# Board_V03.net
KiCad netlist of a schematic drawn in EAGLE
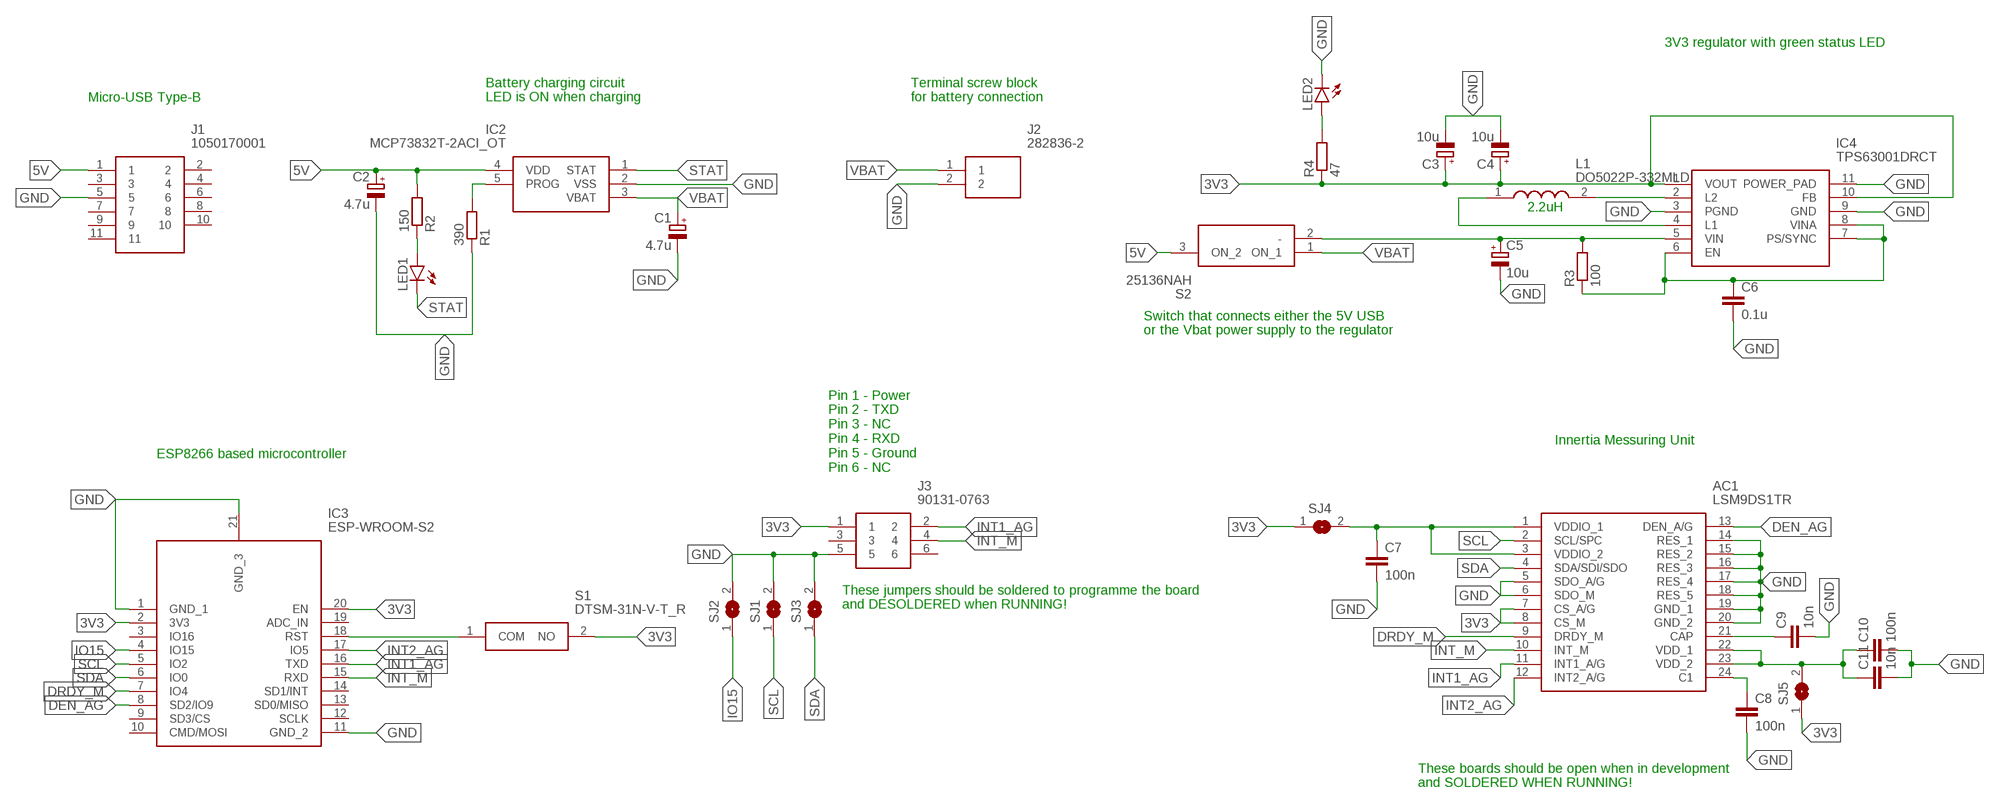
[diagram p0: schematic, sheet 1]

(export (version "E")
  (design (tool "Eeschema 10.0.6"))
  (components
    (comp (ref "AC1")
      (value "LSM9DS1TR")
      (footprint "eagle-import:LGA-24L(3X3.5X1MM)")
      (fields (field (name "MOUSER_PART_NUMBER") "511-LSM9DS1TR") (field (name "RS_PART_NUMBER") "1660908"))
      (libsource (lib "eagle-import") (part "LSM9DS1TR"))
    )
    (comp (ref "C1")
      (value "4.7u")
      (footprint "eagle-import:D_7343-31R")
      (libsource (lib "eagle-import") (part "CPOL-EUD/7343-31R"))
    )
    (comp (ref "C2")
      (value "4.7u")
      (footprint "eagle-import:D_7343-31R")
      (libsource (lib "eagle-import") (part "CPOL-EUD/7343-31R"))
    )
    (comp (ref "C3")
      (value "10u")
      (footprint "eagle-import:D_7343-31R")
      (libsource (lib "eagle-import") (part "CPOL-EUD/7343-31R"))
    )
    (comp (ref "C4")
      (value "10u")
      (footprint "eagle-import:D_7343-31R")
      (libsource (lib "eagle-import") (part "CPOL-EUD/7343-31R"))
    )
    (comp (ref "C5")
      (value "10u")
      (footprint "eagle-import:D_7343-31R")
      (libsource (lib "eagle-import") (part "CPOL-EUD/7343-31R"))
    )
    (comp (ref "C6")
      (value "0.1u")
      (footprint "eagle-import:C0402")
      (libsource (lib "eagle-import") (part "C-EUC0402"))
    )
    (comp (ref "C7")
      (value "100n")
      (footprint "eagle-import:C0805")
      (libsource (lib "eagle-import") (part "C-EUC0805"))
    )
    (comp (ref "C8")
      (value "100n")
      (footprint "eagle-import:C0805")
      (libsource (lib "eagle-import") (part "C-EUC0805"))
    )
    (comp (ref "C9")
      (value "10n")
      (footprint "eagle-import:C0805")
      (libsource (lib "eagle-import") (part "C-EUC0805"))
    )
    (comp (ref "C10")
      (value "100n")
      (footprint "eagle-import:C0805")
      (libsource (lib "eagle-import") (part "C-EUC0805"))
    )
    (comp (ref "C11")
      (value "10n")
      (footprint "eagle-import:C0805")
      (libsource (lib "eagle-import") (part "C-EUC0805"))
    )
    (comp (ref "IC2")
      (value "MCP73832T-2ACI_OT")
      (footprint "eagle-import:SOT95P270X145-5N")
      (fields
        (field (name "MANUFACTURER_PART_NUMBER") "MCP73832T-2ACI/OT")
        (field (name "MOUSER_PART_NUMBER") "579-MCP73832T-2ACIOT")
        (field (name "RS_PART_NUMBER") "9122897")
      )
      (libsource (lib "eagle-import") (part "MCP73832T-2ACI_OT"))
    )
    (comp (ref "IC3")
      (value "ESP-WROOM-S2")
      (footprint "eagle-import:QFN150P1600X1700X315-21N")
      (libsource (lib "eagle-import") (part "ESP-WROOM-S2"))
    )
    (comp (ref "IC4")
      (value "TPS63001DRCT")
      (footprint "eagle-import:SON50P300X300X100-11N")
      (fields (field (name "RS_PART_NUMBER") "7968405"))
      (libsource (lib "eagle-import") (part "TPS63001DRCT"))
    )
    (comp (ref "J1")
      (value "1050170001")
      (footprint "eagle-import:MICROUSB-BTYPE")
      (libsource (lib "eagle-import") (part "1050170001"))
    )
    (comp (ref "J2")
      (value "282836-2")
      (footprint "eagle-import:SHDR2W100P0X500_1X2_1000X820X1")
      (fields (field (name "MOUSER_PART_NUMBER") "571-2828362") (field (name "RS_PART_NUMBER") "1354983"))
      (libsource (lib "eagle-import") (part "282836-2"))
    )
    (comp (ref "J3")
      (value "90131-0763")
      (footprint "eagle-import:HDRV6W90P254_2X3_762X500X560P")
      (fields (field (name "MOUSER_PART_NUMBER") "538-90131-0763") (field (name "RS_PART_NUMBER") "3606443P"))
      (libsource (lib "eagle-import") (part "90131-0763"))
    )
    (comp (ref "L1")
      (value "DO5022P-332MLD")
      (footprint "eagle-import:DO5022P-104MLD")
      (fields (field (name "MOUSER_PART_NUMBER") "994-DO5022P-332MLD"))
      (libsource (lib "eagle-import") (part "DO5022P-332MLD"))
    )
    (comp (ref "LED1")
      (value "LED5MM")
      (footprint "eagle-import:LED5MM")
      (libsource (lib "eagle-import") (part "LED5MM"))
    )
    (comp (ref "LED2")
      (value "LED5MM")
      (footprint "eagle-import:LED5MM")
      (libsource (lib "eagle-import") (part "LED5MM"))
    )
    (comp (ref "R1")
      (value "390")
      (footprint "eagle-import:R0805")
      (libsource (lib "eagle-import") (part "R-EU_R0805"))
    )
    (comp (ref "R2")
      (value "150")
      (footprint "eagle-import:R0805")
      (libsource (lib "eagle-import") (part "R-EU_R0805"))
    )
    (comp (ref "R3")
      (value "100")
      (footprint "eagle-import:R0805")
      (libsource (lib "eagle-import") (part "R-EU_R0805"))
    )
    (comp (ref "R4")
      (value "47")
      (footprint "eagle-import:R0805")
      (libsource (lib "eagle-import") (part "R-EU_R0805"))
    )
    (comp (ref "S1")
      (value "DTSM-31N-V-T_R")
      (footprint "eagle-import:DTSM32NVTR")
      (fields
        (field (name "MANUFACTURER_PART_NUMBER") "DTSM-31N-V-T/R")
        (field (name "MOUSER_PART_NUMBER") "113-DTSM31NVTR")
      )
      (libsource (lib "eagle-import") (part "DTSM-31N-V-T_R"))
    )
    (comp (ref "S2")
      (value "25136NAH")
      (footprint "eagle-import:25136NAH")
      (fields (field (name "MOUSER_PART_NUMBER") "642-25136NAH") (field (name "RS_PART_NUMBER") "0339673A"))
      (libsource (lib "eagle-import") (part "25136NAH"))
    )
    (comp (ref "SJ1")
      (value "SJW")
      (footprint "eagle-import:SJW")
      (libsource (lib "eagle-import") (part "SJW"))
    )
    (comp (ref "SJ2")
      (value "SJW")
      (footprint "eagle-import:SJW")
      (libsource (lib "eagle-import") (part "SJW"))
    )
    (comp (ref "SJ3")
      (value "SJW")
      (footprint "eagle-import:SJW")
      (libsource (lib "eagle-import") (part "SJW"))
    )
    (comp (ref "SJ4")
      (value "SJW")
      (footprint "eagle-import:SJW")
      (libsource (lib "eagle-import") (part "SJW"))
    )
    (comp (ref "SJ5")
      (value "SJW")
      (footprint "eagle-import:SJW")
      (libsource (lib "eagle-import") (part "SJW"))
    )
  )
  (nets
    (net (code "1") (name "3V3") (class "Default")
      (node (ref "AC1") (pin "7") (pinfunction "CS_A/G_7") (pintype "bidirectional"))
      (node (ref "AC1") (pin "8") (pinfunction "CS_M_8") (pintype "bidirectional"))
      (node (ref "C3") (pin "+") (pinfunction "+_+") (pintype "passive"))
      (node (ref "C4") (pin "+") (pinfunction "+_+") (pintype "passive"))
      (node (ref "IC3") (pin "2") (pinfunction "3V3_2") (pintype "power_in"))
      (node (ref "IC3") (pin "20") (pinfunction "EN_20") (pintype "bidirectional"))
      (node (ref "IC4") (pin "1") (pinfunction "VOUT_1") (pintype "bidirectional"))
      (node (ref "IC4") (pin "10") (pinfunction "FB_10") (pintype "bidirectional"))
      (node (ref "J3") (pin "1") (pinfunction "1_1") (pintype "bidirectional"))
      (node (ref "R4") (pin "1") (pinfunction "1_1") (pintype "passive"))
      (node (ref "S1") (pin "2") (pinfunction "NO_2") (pintype "bidirectional"))
      (node (ref "SJ4") (pin "1") (pinfunction "1_1") (pintype "passive"))
      (node (ref "SJ5") (pin "1") (pinfunction "1_1") (pintype "passive"))
    )
    (net (code "2") (name "5V") (class "Default")
      (node (ref "C2") (pin "+") (pinfunction "+_+") (pintype "passive"))
      (node (ref "IC2") (pin "4") (pinfunction "VDD_4") (pintype "power_in"))
      (node (ref "J1") (pin "1") (pinfunction "1_1") (pintype "bidirectional"))
      (node (ref "R2") (pin "2") (pinfunction "2_2") (pintype "passive"))
      (node (ref "S2") (pin "3") (pinfunction "ON_2_3") (pintype "bidirectional"))
    )
    (net (code "3") (name "DEN_AG") (class "Default")
      (node (ref "AC1") (pin "13") (pinfunction "DEN_A/G_13") (pintype "bidirectional"))
      (node (ref "IC3") (pin "8") (pinfunction "SD2/IO9_8") (pintype "bidirectional"))
    )
    (net (code "4") (name "DRDY_M") (class "Default")
      (node (ref "AC1") (pin "9") (pinfunction "DRDY_M_9") (pintype "bidirectional"))
      (node (ref "IC3") (pin "7") (pinfunction "IO4_7") (pintype "bidirectional"))
    )
    (net (code "5") (name "GND") (class "Default")
      (node (ref "AC1") (pin "14") (pinfunction "RES_1_14") (pintype "power_in"))
      (node (ref "AC1") (pin "15") (pinfunction "RES_2_15") (pintype "power_in"))
      (node (ref "AC1") (pin "16") (pinfunction "RES_3_16") (pintype "power_in"))
      (node (ref "AC1") (pin "17") (pinfunction "RES_4_17") (pintype "power_in"))
      (node (ref "AC1") (pin "18") (pinfunction "RES_5_18") (pintype "power_in"))
      (node (ref "AC1") (pin "19") (pinfunction "GND_1_19") (pintype "power_in"))
      (node (ref "AC1") (pin "20") (pinfunction "GND_2_20") (pintype "power_in"))
      (node (ref "AC1") (pin "5") (pinfunction "SDO_A/G_5") (pintype "output"))
      (node (ref "AC1") (pin "6") (pinfunction "SDO_M_6") (pintype "output"))
      (node (ref "C1") (pin "-") (pinfunction "-_-") (pintype "passive"))
      (node (ref "C10") (pin "2") (pinfunction "2_2") (pintype "passive"))
      (node (ref "C11") (pin "2") (pinfunction "2_2") (pintype "passive"))
      (node (ref "C2") (pin "-") (pinfunction "-_-") (pintype "passive"))
      (node (ref "C3") (pin "-") (pinfunction "-_-") (pintype "passive"))
      (node (ref "C4") (pin "-") (pinfunction "-_-") (pintype "passive"))
      (node (ref "C5") (pin "-") (pinfunction "-_-") (pintype "passive"))
      (node (ref "C6") (pin "2") (pinfunction "2_2") (pintype "passive"))
      (node (ref "C7") (pin "2") (pinfunction "2_2") (pintype "passive"))
      (node (ref "C8") (pin "2") (pinfunction "2_2") (pintype "passive"))
      (node (ref "C9") (pin "2") (pinfunction "2_2") (pintype "passive"))
      (node (ref "IC2") (pin "2") (pinfunction "VSS_2") (pintype "power_in"))
      (node (ref "IC3") (pin "1") (pinfunction "GND_1_1") (pintype "power_in"))
      (node (ref "IC3") (pin "11") (pinfunction "GND_2_11") (pintype "power_in"))
      (node (ref "IC3") (pin "21") (pinfunction "GND_3_21") (pintype "power_in"))
      (node (ref "IC4") (pin "11") (pinfunction "POWER_PAD_11") (pintype "bidirectional"))
      (node (ref "IC4") (pin "3") (pinfunction "PGND_3") (pintype "bidirectional"))
      (node (ref "IC4") (pin "9") (pinfunction "GND_9") (pintype "bidirectional"))
      (node (ref "J1") (pin "5") (pinfunction "5_5") (pintype "bidirectional"))
      (node (ref "J2") (pin "2") (pinfunction "2_2") (pintype "bidirectional"))
      (node (ref "J3") (pin "5") (pinfunction "5_5") (pintype "bidirectional"))
      (node (ref "LED2") (pin "K") (pinfunction "C_K") (pintype "passive"))
      (node (ref "R1") (pin "1") (pinfunction "1_1") (pintype "passive"))
      (node (ref "SJ1") (pin "2") (pinfunction "2_2") (pintype "passive"))
      (node (ref "SJ2") (pin "2") (pinfunction "2_2") (pintype "passive"))
      (node (ref "SJ3") (pin "2") (pinfunction "2_2") (pintype "passive"))
    )
    (net (code "6") (name "INT1_AG") (class "Default")
      (node (ref "AC1") (pin "11") (pinfunction "INT1_A/G_11") (pintype "bidirectional"))
      (node (ref "IC3") (pin "16") (pinfunction "TXD_16") (pintype "bidirectional"))
      (node (ref "J3") (pin "2") (pinfunction "2_2") (pintype "bidirectional"))
    )
    (net (code "7") (name "INT2_AG") (class "Default")
      (node (ref "AC1") (pin "12") (pinfunction "INT2_A/G_12") (pintype "bidirectional"))
      (node (ref "IC3") (pin "17") (pinfunction "IO5_17") (pintype "bidirectional"))
    )
    (net (code "8") (name "INT_M") (class "Default")
      (node (ref "AC1") (pin "10") (pinfunction "INT_M_10") (pintype "bidirectional"))
      (node (ref "IC3") (pin "15") (pinfunction "RXD_15") (pintype "bidirectional"))
      (node (ref "J3") (pin "4") (pinfunction "4_4") (pintype "bidirectional"))
    )
    (net (code "9") (name "IO15") (class "Default")
      (node (ref "IC3") (pin "4") (pinfunction "IO15_4") (pintype "bidirectional"))
      (node (ref "SJ2") (pin "1") (pinfunction "1_1") (pintype "passive"))
    )
    (net (code "10") (name "Net-(AC1-C1)") (class "Default")
      (node (ref "AC1") (pin "24") (pinfunction "C1_24") (pintype "bidirectional"))
      (node (ref "C8") (pin "1") (pinfunction "1_1") (pintype "passive"))
    )
    (net (code "11") (name "Net-(AC1-CAP)") (class "Default")
      (node (ref "AC1") (pin "21") (pinfunction "CAP_21") (pintype "power_in"))
      (node (ref "C9") (pin "1") (pinfunction "1_1") (pintype "passive"))
    )
    (net (code "12") (name "Net-(AC1-VDDIO_1)") (class "Default")
      (node (ref "AC1") (pin "1") (pinfunction "VDDIO_1_1") (pintype "power_in"))
      (node (ref "AC1") (pin "3") (pinfunction "VDDIO_2_3") (pintype "power_in"))
      (node (ref "C7") (pin "1") (pinfunction "1_1") (pintype "passive"))
      (node (ref "SJ4") (pin "2") (pinfunction "2_2") (pintype "passive"))
    )
    (net (code "13") (name "Net-(AC1-VDD_1)") (class "Default")
      (node (ref "AC1") (pin "22") (pinfunction "VDD_1_22") (pintype "power_in"))
      (node (ref "AC1") (pin "23") (pinfunction "VDD_2_23") (pintype "power_in"))
      (node (ref "C10") (pin "1") (pinfunction "1_1") (pintype "passive"))
      (node (ref "C11") (pin "1") (pinfunction "1_1") (pintype "passive"))
      (node (ref "SJ5") (pin "2") (pinfunction "2_2") (pintype "passive"))
    )
    (net (code "14") (name "Net-(IC2-PROG)") (class "Default")
      (node (ref "IC2") (pin "5") (pinfunction "PROG_5") (pintype "bidirectional"))
      (node (ref "R1") (pin "2") (pinfunction "2_2") (pintype "passive"))
    )
    (net (code "15") (name "Net-(IC3-RST)") (class "Default")
      (node (ref "IC3") (pin "18") (pinfunction "RST_18") (pintype "input"))
      (node (ref "S1") (pin "1") (pinfunction "COM_1") (pintype "bidirectional"))
    )
    (net (code "16") (name "Net-(IC4-EN)") (class "Default")
      (node (ref "C6") (pin "1") (pinfunction "1_1") (pintype "passive"))
      (node (ref "IC4") (pin "6") (pinfunction "EN_6") (pintype "bidirectional"))
      (node (ref "IC4") (pin "7") (pinfunction "PS/SYNC_7") (pintype "bidirectional"))
      (node (ref "IC4") (pin "8") (pinfunction "VINA_8") (pintype "bidirectional"))
      (node (ref "R3") (pin "1") (pinfunction "1_1") (pintype "passive"))
    )
    (net (code "17") (name "Net-(IC4-L1)") (class "Default")
      (node (ref "IC4") (pin "4") (pinfunction "L1_4") (pintype "bidirectional"))
      (node (ref "L1") (pin "1") (pinfunction "1_1") (pintype "bidirectional"))
    )
    (net (code "18") (name "Net-(IC4-L2)") (class "Default")
      (node (ref "IC4") (pin "2") (pinfunction "L2_2") (pintype "bidirectional"))
      (node (ref "L1") (pin "2") (pinfunction "2_2") (pintype "bidirectional"))
    )
    (net (code "19") (name "Net-(IC4-VIN)") (class "Default")
      (node (ref "C5") (pin "+") (pinfunction "+_+") (pintype "passive"))
      (node (ref "IC4") (pin "5") (pinfunction "VIN_5") (pintype "bidirectional"))
      (node (ref "R3") (pin "2") (pinfunction "2_2") (pintype "passive"))
      (node (ref "S2") (pin "2") (pinfunction "-_2") (pintype "bidirectional"))
    )
    (net (code "20") (name "Net-(LED1-PadA)") (class "Default")
      (node (ref "LED1") (pin "A") (pinfunction "A_A") (pintype "passive"))
      (node (ref "R2") (pin "1") (pinfunction "1_1") (pintype "passive"))
    )
    (net (code "21") (name "Net-(LED2-PadA)") (class "Default")
      (node (ref "LED2") (pin "A") (pinfunction "A_A") (pintype "passive"))
      (node (ref "R4") (pin "2") (pinfunction "2_2") (pintype "passive"))
    )
    (net (code "22") (name "SCL") (class "Default")
      (node (ref "AC1") (pin "2") (pinfunction "SCL/SPC_2") (pintype "output"))
      (node (ref "IC3") (pin "5") (pinfunction "IO2_5") (pintype "bidirectional"))
      (node (ref "SJ1") (pin "1") (pinfunction "1_1") (pintype "passive"))
    )
    (net (code "23") (name "SDA") (class "Default")
      (node (ref "AC1") (pin "4") (pinfunction "SDA/SDI/SDO_4") (pintype "bidirectional"))
      (node (ref "IC3") (pin "6") (pinfunction "IO0_6") (pintype "bidirectional"))
      (node (ref "SJ3") (pin "1") (pinfunction "1_1") (pintype "passive"))
    )
    (net (code "24") (name "STAT") (class "Default")
      (node (ref "IC2") (pin "1") (pinfunction "STAT_1") (pintype "bidirectional"))
      (node (ref "LED1") (pin "K") (pinfunction "C_K") (pintype "passive"))
    )
    (net (code "25") (name "VBAT") (class "Default")
      (node (ref "C1") (pin "+") (pinfunction "+_+") (pintype "passive"))
      (node (ref "IC2") (pin "3") (pinfunction "VBAT_3") (pintype "bidirectional"))
      (node (ref "J2") (pin "1") (pinfunction "1_1") (pintype "bidirectional"))
      (node (ref "S2") (pin "1") (pinfunction "ON_1_1") (pintype "bidirectional"))
    )
    (net (code "26") (name "unconnected-(IC3-ADC_IN-Pad19)") (class "Default")
      (node (ref "IC3") (pin "19") (pinfunction "ADC_IN_19") (pintype "input"))
    )
    (net (code "27") (name "unconnected-(IC3-CMD{slash}MOSI-Pad10)") (class "Default")
      (node (ref "IC3") (pin "10") (pinfunction "CMD/MOSI_10") (pintype "bidirectional"))
    )
    (net (code "28") (name "unconnected-(IC3-IO16-Pad3)") (class "Default")
      (node (ref "IC3") (pin "3") (pinfunction "IO16_3") (pintype "bidirectional"))
    )
    (net (code "29") (name "unconnected-(IC3-SCLK-Pad12)") (class "Default")
      (node (ref "IC3") (pin "12") (pinfunction "SCLK_12") (pintype "bidirectional"))
    )
    (net (code "30") (name "unconnected-(IC3-SD0{slash}MISO-Pad13)") (class "Default")
      (node (ref "IC3") (pin "13") (pinfunction "SD0/MISO_13") (pintype "bidirectional"))
    )
    (net (code "31") (name "unconnected-(IC3-SD1{slash}INT-Pad14)") (class "Default")
      (node (ref "IC3") (pin "14") (pinfunction "SD1/INT_14") (pintype "bidirectional"))
    )
    (net (code "32") (name "unconnected-(IC3-SD3{slash}CS-Pad9)") (class "Default")
      (node (ref "IC3") (pin "9") (pinfunction "SD3/CS_9") (pintype "bidirectional"))
    )
    (net (code "33") (name "unconnected-(J1-Pad2)") (class "Default")
      (node (ref "J1") (pin "2") (pinfunction "2_2") (pintype "bidirectional"))
    )
    (net (code "34") (name "unconnected-(J1-Pad3)") (class "Default")
      (node (ref "J1") (pin "3") (pinfunction "3_3") (pintype "bidirectional"))
    )
    (net (code "35") (name "unconnected-(J1-Pad4)") (class "Default")
      (node (ref "J1") (pin "4") (pinfunction "4_4") (pintype "bidirectional"))
    )
    (net (code "36") (name "unconnected-(J1-Pad6)") (class "Default")
      (node (ref "J1") (pin "6") (pinfunction "6_6") (pintype "bidirectional"))
    )
    (net (code "37") (name "unconnected-(J1-Pad7)") (class "Default")
      (node (ref "J1") (pin "7") (pinfunction "7_7") (pintype "bidirectional"))
    )
    (net (code "38") (name "unconnected-(J1-Pad8)") (class "Default")
      (node (ref "J1") (pin "8") (pinfunction "8_8") (pintype "bidirectional"))
    )
    (net (code "39") (name "unconnected-(J1-Pad9)") (class "Default")
      (node (ref "J1") (pin "9") (pinfunction "9_9") (pintype "bidirectional"))
    )
    (net (code "40") (name "unconnected-(J1-Pad10)") (class "Default")
      (node (ref "J1") (pin "10") (pinfunction "10_10") (pintype "bidirectional"))
    )
    (net (code "41") (name "unconnected-(J1-Pad11)") (class "Default")
      (node (ref "J1") (pin "11") (pinfunction "11_11") (pintype "bidirectional"))
    )
    (net (code "42") (name "unconnected-(J3-Pad3)") (class "Default")
      (node (ref "J3") (pin "3") (pinfunction "3_3") (pintype "bidirectional"))
    )
    (net (code "43") (name "unconnected-(J3-Pad6)") (class "Default")
      (node (ref "J3") (pin "6") (pinfunction "6_6") (pintype "bidirectional"))
    )
  )
)
